# HandHeld_O2_Analyzer.net
KiCad netlist of a schematic drawn in EAGLE
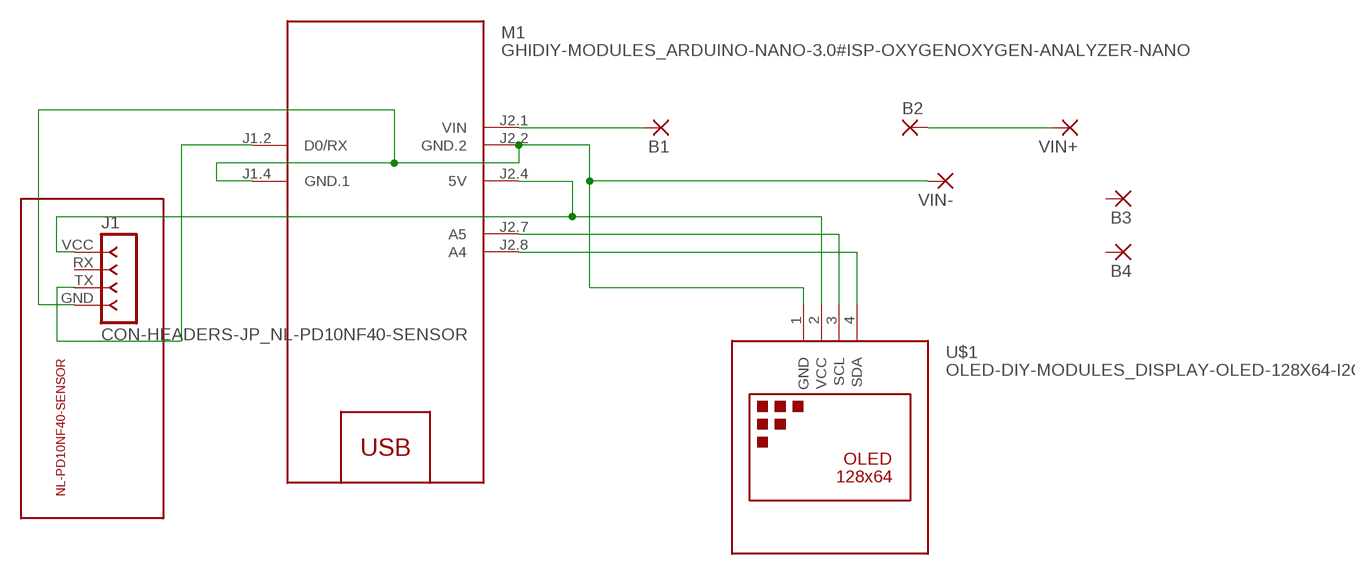
[diagram p0: schematic, sheet 1]

(export (version "E")
  (design (tool "Eeschema 10.0.6"))
  (components
    (comp (ref "B1")
      (value "2,54/0,8")
      (footprint "eagle-import:2,54_0,8")
      (libsource (lib "eagle-import") (part "2,54/0,8"))
    )
    (comp (ref "B2")
      (value "2,54/0,8")
      (footprint "eagle-import:2,54_0,8")
      (libsource (lib "eagle-import") (part "2,54/0,8"))
    )
    (comp (ref "B3")
      (value "2,54/0,8")
      (footprint "eagle-import:2,54_0,8")
      (libsource (lib "eagle-import") (part "2,54/0,8"))
    )
    (comp (ref "B4")
      (value "2,54/0,8")
      (footprint "eagle-import:2,54_0,8")
      (libsource (lib "eagle-import") (part "2,54/0,8"))
    )
    (comp (ref "J1")
      (value "CON-HEADERS-JP_NL-PD10NF40-SENSOR")
      (footprint "eagle-import:CON-HEADERS-JP_NL-PD10NF40-SENSOR")
      (libsource (lib "eagle-import") (part "CON-HEADERS-JP_NL-PD10NF40-SENSOR"))
    )
    (comp (ref "M1")
      (value "GHIDIY-MODULES_ARDUINO-NANO-3.0#ISP-OXYGENOXYGEN-ANALYZER-NANO")
      (footprint "eagle-import:GHIDIY-MODULES_ARDUINO-NANO-3.0#ISP-OXYGEN")
      (libsource (lib "eagle-import") (part "GHIDIY-MODULES_ARDUINO-NANO-3.0#ISP-OXYGEN?OXYGEN-ANALYZER-NANO"))
    )
    (comp (ref "U$1")
      (value "OLED-DIY-MODULES_DISPLAY-OLED-128X64-I2C")
      (footprint "eagle-import:OLED-DIY-MODULES_DISPLAY-OLED-128X64-I2C")
      (libsource (lib "eagle-import") (part "OLED-DIY-MODULES_DISPLAY-OLED-128X64-I2C"))
    )
    (comp (ref "VIN+")
      (value "WIREPAD_2,54/0,8")
      (footprint "eagle-import:WIREPAD_2,54_0,8")
      (libsource (lib "eagle-import") (part "WIREPAD_2,54/0,8"))
    )
    (comp (ref "VIN-")
      (value "WIREPAD_2,54/0,8")
      (footprint "eagle-import:WIREPAD_2,54_0,8")
      (libsource (lib "eagle-import") (part "WIREPAD_2,54/0,8"))
    )
  )
  (nets
    (net (code "1") (name "Net-(B1-P)") (class "Default")
      (node (ref "B1") (pin "1") (pinfunction "P_1") (pintype "passive"))
      (node (ref "M1") (pin "J2.1") (pinfunction "VIN_J2.1") (pintype "power_in"))
    )
    (net (code "2") (name "Net-(B2-P)") (class "Default")
      (node (ref "B2") (pin "1") (pinfunction "P_1") (pintype "passive"))
      (node (ref "VIN+") (pin "1") (pinfunction "P_1") (pintype "passive"))
    )
    (net (code "3") (name "Net-(M1-5V)") (class "Default")
      (node (ref "J1") (pin "VCC") (pinfunction "VCC_VCC") (pintype "passive"))
      (node (ref "M1") (pin "J2.4") (pinfunction "5V_J2.4") (pintype "power_in"))
      (node (ref "U$1") (pin "2") (pinfunction "VCC_2") (pintype "power_in"))
    )
    (net (code "4") (name "Net-(M1-A4)") (class "Default")
      (node (ref "M1") (pin "J2.8") (pinfunction "A4_J2.8") (pintype "bidirectional"))
      (node (ref "U$1") (pin "4") (pinfunction "SDA_4") (pintype "bidirectional"))
    )
    (net (code "5") (name "Net-(M1-A5)") (class "Default")
      (node (ref "M1") (pin "J2.7") (pinfunction "A5_J2.7") (pintype "bidirectional"))
      (node (ref "U$1") (pin "3") (pinfunction "SCL_3") (pintype "bidirectional"))
    )
    (net (code "6") (name "Net-(M1-D0{slash}RX)") (class "Default")
      (node (ref "J1") (pin "TX") (pinfunction "TX_TX") (pintype "passive"))
      (node (ref "M1") (pin "J1.2") (pinfunction "D0/RX_J1.2") (pintype "bidirectional"))
    )
    (net (code "7") (name "Net-(M1-GND.1)") (class "Default")
      (node (ref "J1") (pin "GND") (pinfunction "GND_GND") (pintype "passive"))
      (node (ref "M1") (pin "J1.4") (pinfunction "GND.1_J1.4") (pintype "power_in"))
      (node (ref "M1") (pin "J2.2") (pinfunction "GND.2_J2.2") (pintype "power_in"))
      (node (ref "U$1") (pin "1") (pinfunction "GND_1") (pintype "power_in"))
      (node (ref "VIN-") (pin "1") (pinfunction "P_1") (pintype "passive"))
    )
    (net (code "8") (name "unconnected-(B3-P-Pad1)") (class "Default")
      (node (ref "B3") (pin "1") (pinfunction "P_1") (pintype "passive"))
    )
    (net (code "9") (name "unconnected-(B4-P-Pad1)") (class "Default")
      (node (ref "B4") (pin "1") (pinfunction "P_1") (pintype "passive"))
    )
    (net (code "10") (name "unconnected-(J1-PadRX)") (class "Default")
      (node (ref "J1") (pin "RX") (pinfunction "RX_RX") (pintype "passive"))
    )
  )
)
